# BUT.net
KiCad netlist of a schematic drawn in Altium Designer
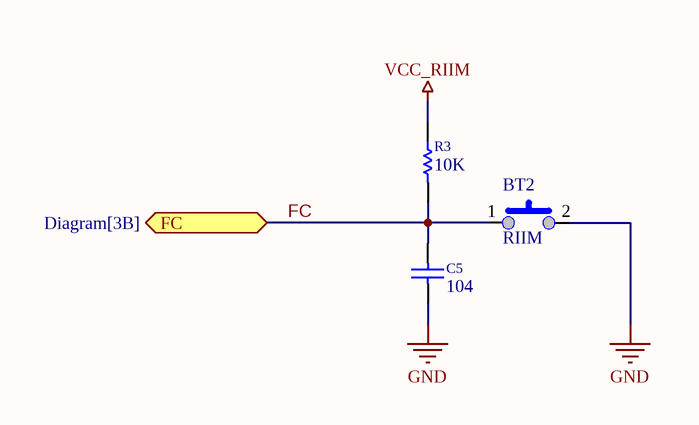
[diagram p0: BUT.SchDoc]

(export (version "E")
  (design (tool "Eeschema 10.0.6"))
  (components
    (comp (ref "BT2")
      (value "RIIM")
      (footprint "B3U-1000P")
      (libsource (lib "VPMyLibrary") (part "Button_2p"))
    )
    (comp (ref "C5")
      (value "104")
      (footprint "C2012-0805")
      (description "Capacitor")
      (fields (field (name "PUBLISHER") "Hoang Nguyen"))
      (libsource (lib "VPMyLibrary") (part "Cap {lt}SMD{gt}"))
    )
    (comp (ref "R3")
      (value "10K")
      (footprint "R2012-0805")
      (description "Resistor")
      (fields (field (name "PUBLISHER") "Hoang Nguyen"))
      (libsource (lib "VPMyLibrary") (part "Resistor {lt}SMD{gt}"))
    )
  )
  (nets
    (net (code "1") (name "/FC") (class "Default")
      (node (ref "BT2") (pin "1") (pinfunction "1_1") (pintype "passive"))
      (node (ref "C5") (pin "1") (pinfunction "1_1") (pintype "passive"))
      (node (ref "R3") (pin "2") (pinfunction "2_2") (pintype "passive"))
    )
    (net (code "2") (name "GND") (class "Default")
      (node (ref "BT2") (pin "2") (pinfunction "2_2") (pintype "passive"))
      (node (ref "C5") (pin "2") (pinfunction "2_2") (pintype "passive"))
    )
    (net (code "3") (name "VCC_RIIM") (class "Default")
      (node (ref "R3") (pin "1") (pinfunction "1_1") (pintype "passive"))
    )
  )
)
